# MSO-demo-board.net
KiCad netlist of a schematic drawn in EAGLE
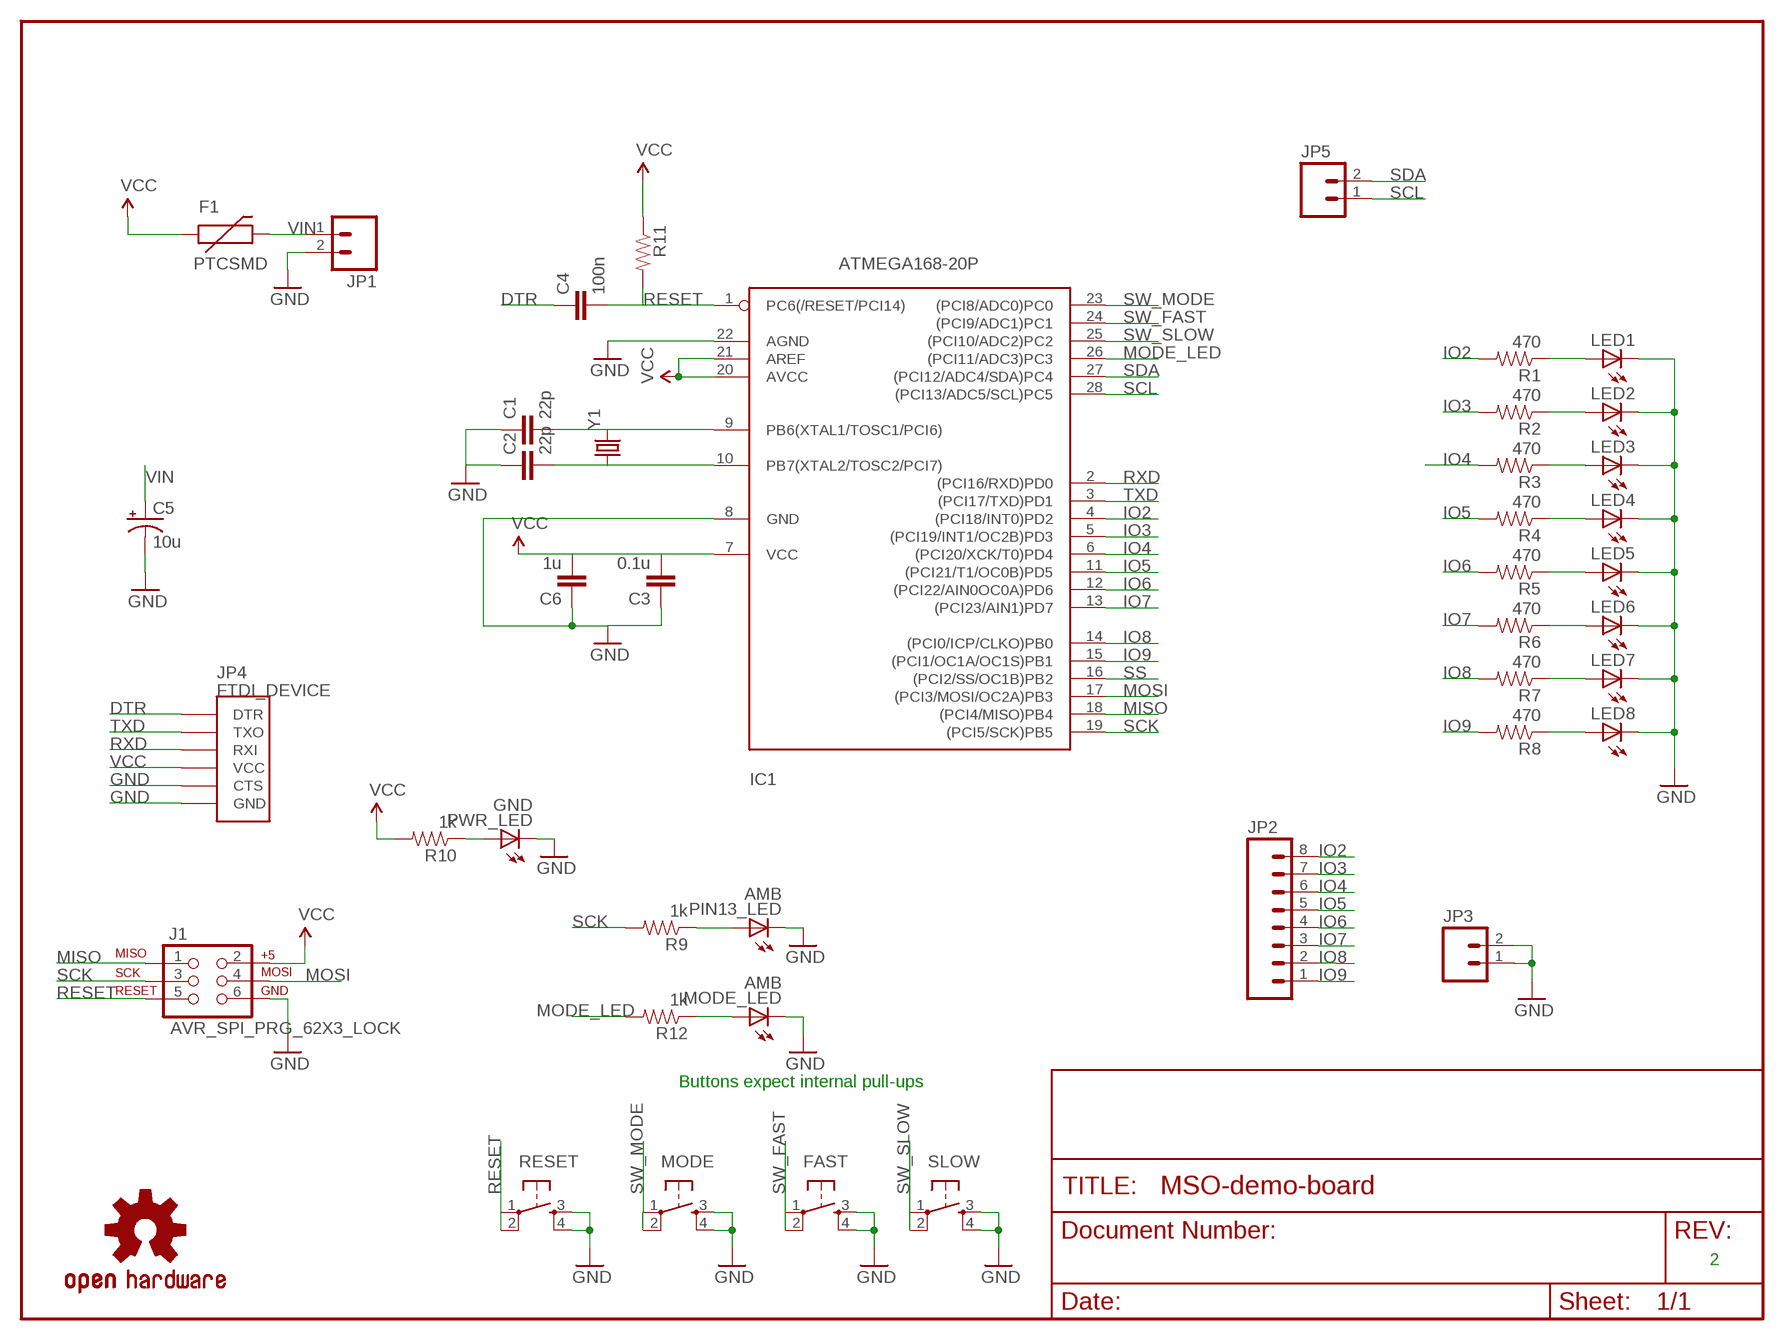
[diagram p0: schematic, sheet 1]

(export (version "E")
  (design (tool "Eeschema 10.0.6"))
  (components
    (comp (ref "C1")
      (value "22p")
      (footprint "eagle-import:1206")
      (libsource (lib "eagle-import") (part "CAP1206"))
    )
    (comp (ref "C2")
      (value "22p")
      (footprint "eagle-import:1206")
      (libsource (lib "eagle-import") (part "CAP1206"))
    )
    (comp (ref "C3")
      (value "0.1u")
      (footprint "eagle-import:1206")
      (libsource (lib "eagle-import") (part "CAP1206"))
    )
    (comp (ref "C4")
      (value "100n")
      (footprint "eagle-import:1206")
      (libsource (lib "eagle-import") (part "CAP1206"))
    )
    (comp (ref "C5")
      (value "10u")
      (footprint "eagle-import:CT7343")
      (libsource (lib "eagle-import") (part "CPOL-USCT7343"))
    )
    (comp (ref "C6")
      (value "1u")
      (footprint "eagle-import:1206")
      (libsource (lib "eagle-import") (part "CAP1206"))
    )
    (comp (ref "F1")
      (value "PTCSMD")
      (footprint "eagle-import:PTC-1206")
      (libsource (lib "eagle-import") (part "PTCSMD"))
    )
    (comp (ref "FAST")
      (value "TAC_SWITCHSMD")
      (footprint "eagle-import:TACTILE_SWITCH_SMD")
      (libsource (lib "eagle-import") (part "TAC_SWITCHSMD"))
    )
    (comp (ref "IC1")
      (value "ATMEGA168-20P")
      (footprint "eagle-import:DIL28-3")
      (libsource (lib "eagle-import") (part "ATMEGA168P-20"))
    )
    (comp (ref "J1")
      (value "AVR_SPI_PRG_62X3_LOCK")
      (footprint "eagle-import:2X3_LOCK")
      (libsource (lib "eagle-import") (part "AVR_SPI_PRG_62X3_LOCK"))
    )
    (comp (ref "JP1")
      (value "M02LOCK")
      (footprint "eagle-import:1X02_LOCK")
      (libsource (lib "eagle-import") (part "M02LOCK"))
    )
    (comp (ref "JP2")
      (value "M08LOCK")
      (footprint "eagle-import:1X08_LOCK")
      (libsource (lib "eagle-import") (part "M08LOCK"))
    )
    (comp (ref "JP3")
      (value "M02LOCK")
      (footprint "eagle-import:1X02_LOCK")
      (libsource (lib "eagle-import") (part "M02LOCK"))
    )
    (comp (ref "JP4")
      (value "FTDI_DEVICE")
      (footprint "eagle-import:FTDI_DEVICE_SIDE")
      (libsource (lib "eagle-import") (part "FTDI_DEVICE"))
    )
    (comp (ref "JP5")
      (value "M02LOCK")
      (footprint "eagle-import:1X02_LOCK")
      (libsource (lib "eagle-import") (part "M02LOCK"))
    )
    (comp (ref "LED1")
      (value "LED1206")
      (footprint "eagle-import:LED-1206")
      (libsource (lib "eagle-import") (part "LED1206"))
    )
    (comp (ref "LED2")
      (value "LED1206")
      (footprint "eagle-import:LED-1206")
      (libsource (lib "eagle-import") (part "LED1206"))
    )
    (comp (ref "LED3")
      (value "LED1206")
      (footprint "eagle-import:LED-1206")
      (libsource (lib "eagle-import") (part "LED1206"))
    )
    (comp (ref "LED4")
      (value "LED1206")
      (footprint "eagle-import:LED-1206")
      (libsource (lib "eagle-import") (part "LED1206"))
    )
    (comp (ref "LED5")
      (value "LED1206")
      (footprint "eagle-import:LED-1206")
      (libsource (lib "eagle-import") (part "LED1206"))
    )
    (comp (ref "LED6")
      (value "LED1206")
      (footprint "eagle-import:LED-1206")
      (libsource (lib "eagle-import") (part "LED1206"))
    )
    (comp (ref "LED7")
      (value "LED1206")
      (footprint "eagle-import:LED-1206")
      (libsource (lib "eagle-import") (part "LED1206"))
    )
    (comp (ref "LED8")
      (value "LED1206")
      (footprint "eagle-import:LED-1206")
      (libsource (lib "eagle-import") (part "LED1206"))
    )
    (comp (ref "MODE")
      (value "TAC_SWITCHSMD")
      (footprint "eagle-import:TACTILE_SWITCH_SMD")
      (libsource (lib "eagle-import") (part "TAC_SWITCHSMD"))
    )
    (comp (ref "MODE_LED")
      (value "AMB")
      (footprint "eagle-import:LED-1206")
      (libsource (lib "eagle-import") (part "LED1206"))
    )
    (comp (ref "PIN13_LED")
      (value "AMB")
      (footprint "eagle-import:LED-1206")
      (libsource (lib "eagle-import") (part "LED1206"))
    )
    (comp (ref "PWR_LED")
      (value "GND")
      (footprint "eagle-import:LED-1206")
      (libsource (lib "eagle-import") (part "LED1206"))
    )
    (comp (ref "R1")
      (value "470")
      (footprint "eagle-import:1206")
      (libsource (lib "eagle-import") (part "RESISTOR1206"))
    )
    (comp (ref "R2")
      (value "470")
      (footprint "eagle-import:1206")
      (libsource (lib "eagle-import") (part "RESISTOR1206"))
    )
    (comp (ref "R3")
      (value "470")
      (footprint "eagle-import:1206")
      (libsource (lib "eagle-import") (part "RESISTOR1206"))
    )
    (comp (ref "R4")
      (value "470")
      (footprint "eagle-import:1206")
      (libsource (lib "eagle-import") (part "RESISTOR1206"))
    )
    (comp (ref "R5")
      (value "470")
      (footprint "eagle-import:1206")
      (libsource (lib "eagle-import") (part "RESISTOR1206"))
    )
    (comp (ref "R6")
      (value "470")
      (footprint "eagle-import:1206")
      (libsource (lib "eagle-import") (part "RESISTOR1206"))
    )
    (comp (ref "R7")
      (value "470")
      (footprint "eagle-import:1206")
      (libsource (lib "eagle-import") (part "RESISTOR1206"))
    )
    (comp (ref "R8")
      (value "470")
      (footprint "eagle-import:1206")
      (libsource (lib "eagle-import") (part "RESISTOR1206"))
    )
    (comp (ref "R9")
      (value "1k")
      (footprint "eagle-import:1206")
      (libsource (lib "eagle-import") (part "RESISTOR1206"))
    )
    (comp (ref "R10")
      (value "1k")
      (footprint "eagle-import:1206")
      (libsource (lib "eagle-import") (part "RESISTOR1206"))
    )
    (comp (ref "R11")
      (value "RESISTOR1206")
      (footprint "eagle-import:1206")
      (libsource (lib "eagle-import") (part "RESISTOR1206"))
    )
    (comp (ref "R12")
      (value "1k")
      (footprint "eagle-import:1206")
      (libsource (lib "eagle-import") (part "RESISTOR1206"))
    )
    (comp (ref "RESET")
      (value "TAC_SWITCHSMD")
      (footprint "eagle-import:TACTILE_SWITCH_SMD")
      (libsource (lib "eagle-import") (part "TAC_SWITCHSMD"))
    )
    (comp (ref "SLOW")
      (value "TAC_SWITCHSMD")
      (footprint "eagle-import:TACTILE_SWITCH_SMD")
      (libsource (lib "eagle-import") (part "TAC_SWITCHSMD"))
    )
    (comp (ref "U$1")
      (value "OSHW-LOGOS")
      (footprint "eagle-import:OSHW-LOGO-S")
      (libsource (lib "eagle-import") (part "OSHW-LOGOS"))
    )
    (comp (ref "Y1")
      (value "CRYSTALHC49UV")
      (footprint "eagle-import:HC49U-V")
      (libsource (lib "eagle-import") (part "CRYSTALHC49UV"))
    )
  )
  (nets
    (net (code "1") (name "/DTR") (class "Default")
      (node (ref "C4") (pin "1") (pinfunction "1_1") (pintype "passive"))
      (node (ref "JP4") (pin "P$1") (pinfunction "DTR_P$1") (pintype "bidirectional"))
    )
    (net (code "2") (name "/IO2") (class "Default")
      (node (ref "IC1") (pin "4") (pinfunction "(PCI18/INT0)PD2_4") (pintype "bidirectional"))
      (node (ref "JP2") (pin "8") (pinfunction "8_8") (pintype "passive"))
      (node (ref "R1") (pin "2") (pinfunction "2_2") (pintype "passive"))
    )
    (net (code "3") (name "/IO3") (class "Default")
      (node (ref "IC1") (pin "5") (pinfunction "(PCI19/INT1/OC2B)PD3_5") (pintype "bidirectional"))
      (node (ref "JP2") (pin "7") (pinfunction "7_7") (pintype "passive"))
      (node (ref "R2") (pin "2") (pinfunction "2_2") (pintype "passive"))
    )
    (net (code "4") (name "/IO4") (class "Default")
      (node (ref "IC1") (pin "6") (pinfunction "(PCI20/XCK/T0)PD4_6") (pintype "bidirectional"))
      (node (ref "JP2") (pin "6") (pinfunction "6_6") (pintype "passive"))
      (node (ref "R3") (pin "2") (pinfunction "2_2") (pintype "passive"))
    )
    (net (code "5") (name "/IO5") (class "Default")
      (node (ref "IC1") (pin "11") (pinfunction "(PCI21/T1/OC0B)PD5_11") (pintype "bidirectional"))
      (node (ref "JP2") (pin "5") (pinfunction "5_5") (pintype "passive"))
      (node (ref "R4") (pin "2") (pinfunction "2_2") (pintype "passive"))
    )
    (net (code "6") (name "/IO6") (class "Default")
      (node (ref "IC1") (pin "12") (pinfunction "(PCI22/AIN0OC0A)PD6_12") (pintype "bidirectional"))
      (node (ref "JP2") (pin "4") (pinfunction "4_4") (pintype "passive"))
      (node (ref "R5") (pin "2") (pinfunction "2_2") (pintype "passive"))
    )
    (net (code "7") (name "/IO7") (class "Default")
      (node (ref "IC1") (pin "13") (pinfunction "(PCI23/AIN1)PD7_13") (pintype "bidirectional"))
      (node (ref "JP2") (pin "3") (pinfunction "3_3") (pintype "passive"))
      (node (ref "R6") (pin "2") (pinfunction "2_2") (pintype "passive"))
    )
    (net (code "8") (name "/IO8") (class "Default")
      (node (ref "IC1") (pin "14") (pinfunction "(PCI0/ICP/CLKO)PB0_14") (pintype "bidirectional"))
      (node (ref "JP2") (pin "2") (pinfunction "2_2") (pintype "passive"))
      (node (ref "R7") (pin "2") (pinfunction "2_2") (pintype "passive"))
    )
    (net (code "9") (name "/IO9") (class "Default")
      (node (ref "IC1") (pin "15") (pinfunction "(PCI1/OC1A/OC1S)PB1_15") (pintype "bidirectional"))
      (node (ref "JP2") (pin "1") (pinfunction "1_1") (pintype "passive"))
      (node (ref "R8") (pin "2") (pinfunction "2_2") (pintype "passive"))
    )
    (net (code "10") (name "/MISO") (class "Default")
      (node (ref "IC1") (pin "18") (pinfunction "(PCI4/MISO)PB4_18") (pintype "bidirectional"))
      (node (ref "J1") (pin "1") (pinfunction "1_1") (pintype "passive"))
    )
    (net (code "11") (name "/MODE_LED") (class "Default")
      (node (ref "IC1") (pin "26") (pinfunction "(PCI11/ADC3)PC3_26") (pintype "bidirectional"))
      (node (ref "R12") (pin "2") (pinfunction "2_2") (pintype "passive"))
    )
    (net (code "12") (name "/MOSI") (class "Default")
      (node (ref "IC1") (pin "17") (pinfunction "(PCI3/MOSI/OC2A)PB3_17") (pintype "bidirectional"))
      (node (ref "J1") (pin "4") (pinfunction "4_4") (pintype "passive"))
    )
    (net (code "13") (name "/RESET") (class "Default")
      (node (ref "C4") (pin "2") (pinfunction "2_2") (pintype "passive"))
      (node (ref "IC1") (pin "1") (pinfunction "PC6(/RESET/PCI14)_1") (pintype "bidirectional"))
      (node (ref "J1") (pin "5") (pinfunction "5_5") (pintype "passive"))
      (node (ref "R11") (pin "2") (pinfunction "2_2") (pintype "passive"))
      (node (ref "RESET") (pin "1") (pinfunction "1_1") (pintype "passive"))
      (node (ref "RESET") (pin "2") (pinfunction "2_2") (pintype "passive"))
    )
    (net (code "14") (name "/RXD") (class "Default")
      (node (ref "IC1") (pin "2") (pinfunction "(PCI16/RXD)PD0_2") (pintype "bidirectional"))
      (node (ref "JP4") (pin "P$3") (pinfunction "RXI_P$3") (pintype "bidirectional"))
    )
    (net (code "15") (name "/SCK") (class "Default")
      (node (ref "IC1") (pin "19") (pinfunction "(PCI5/SCK)PB5_19") (pintype "bidirectional"))
      (node (ref "J1") (pin "3") (pinfunction "3_3") (pintype "passive"))
      (node (ref "R9") (pin "2") (pinfunction "2_2") (pintype "passive"))
    )
    (net (code "16") (name "/SCL") (class "Default")
      (node (ref "IC1") (pin "28") (pinfunction "(PCI13/ADC5/SCL)PC5_28") (pintype "bidirectional"))
      (node (ref "JP5") (pin "1") (pinfunction "1_1") (pintype "passive"))
    )
    (net (code "17") (name "/SDA") (class "Default")
      (node (ref "IC1") (pin "27") (pinfunction "(PCI12/ADC4/SDA)PC4_27") (pintype "bidirectional"))
      (node (ref "JP5") (pin "2") (pinfunction "2_2") (pintype "passive"))
    )
    (net (code "18") (name "/SS") (class "Default")
      (node (ref "IC1") (pin "16") (pinfunction "(PCI2/SS/OC1B)PB2_16") (pintype "bidirectional"))
    )
    (net (code "19") (name "/SW_FAST") (class "Default")
      (node (ref "FAST") (pin "1") (pinfunction "1_1") (pintype "passive"))
      (node (ref "FAST") (pin "2") (pinfunction "2_2") (pintype "passive"))
      (node (ref "IC1") (pin "24") (pinfunction "(PCI9/ADC1)PC1_24") (pintype "bidirectional"))
    )
    (net (code "20") (name "/SW_MODE") (class "Default")
      (node (ref "IC1") (pin "23") (pinfunction "(PCI8/ADC0)PC0_23") (pintype "bidirectional"))
      (node (ref "MODE") (pin "1") (pinfunction "1_1") (pintype "passive"))
      (node (ref "MODE") (pin "2") (pinfunction "2_2") (pintype "passive"))
    )
    (net (code "21") (name "/SW_SLOW") (class "Default")
      (node (ref "IC1") (pin "25") (pinfunction "(PCI10/ADC2)PC2_25") (pintype "bidirectional"))
      (node (ref "SLOW") (pin "1") (pinfunction "1_1") (pintype "passive"))
      (node (ref "SLOW") (pin "2") (pinfunction "2_2") (pintype "passive"))
    )
    (net (code "22") (name "/TXD") (class "Default")
      (node (ref "IC1") (pin "3") (pinfunction "(PCI17/TXD)PD1_3") (pintype "bidirectional"))
      (node (ref "JP4") (pin "P$2") (pinfunction "TXO_P$2") (pintype "bidirectional"))
    )
    (net (code "23") (name "/VIN") (class "Default")
      (node (ref "C5") (pin "+") (pinfunction "+_+") (pintype "passive"))
      (node (ref "F1") (pin "2") (pinfunction "2_2") (pintype "bidirectional"))
      (node (ref "JP1") (pin "1") (pinfunction "1_1") (pintype "passive"))
    )
    (net (code "24") (name "GND") (class "Default")
      (node (ref "C1") (pin "1") (pinfunction "1_1") (pintype "passive"))
      (node (ref "C2") (pin "1") (pinfunction "1_1") (pintype "passive"))
      (node (ref "C3") (pin "1") (pinfunction "1_1") (pintype "passive"))
      (node (ref "C5") (pin "-") (pinfunction "-_-") (pintype "passive"))
      (node (ref "C6") (pin "1") (pinfunction "1_1") (pintype "passive"))
      (node (ref "FAST") (pin "3") (pinfunction "3_3") (pintype "passive"))
      (node (ref "FAST") (pin "4") (pinfunction "4_4") (pintype "passive"))
      (node (ref "IC1") (pin "22") (pinfunction "AGND_22") (pintype "bidirectional"))
      (node (ref "IC1") (pin "8") (pinfunction "GND_8") (pintype "bidirectional"))
      (node (ref "J1") (pin "6") (pinfunction "6_6") (pintype "passive"))
      (node (ref "JP1") (pin "2") (pinfunction "2_2") (pintype "passive"))
      (node (ref "JP3") (pin "1") (pinfunction "1_1") (pintype "passive"))
      (node (ref "JP3") (pin "2") (pinfunction "2_2") (pintype "passive"))
      (node (ref "JP4") (pin "P$5") (pinfunction "CTS_P$5") (pintype "bidirectional"))
      (node (ref "JP4") (pin "P$6") (pinfunction "GND_P$6") (pintype "bidirectional"))
      (node (ref "LED1") (pin "C") (pinfunction "C_C") (pintype "passive"))
      (node (ref "LED2") (pin "C") (pinfunction "C_C") (pintype "passive"))
      (node (ref "LED3") (pin "C") (pinfunction "C_C") (pintype "passive"))
      (node (ref "LED4") (pin "C") (pinfunction "C_C") (pintype "passive"))
      (node (ref "LED5") (pin "C") (pinfunction "C_C") (pintype "passive"))
      (node (ref "LED6") (pin "C") (pinfunction "C_C") (pintype "passive"))
      (node (ref "LED7") (pin "C") (pinfunction "C_C") (pintype "passive"))
      (node (ref "LED8") (pin "C") (pinfunction "C_C") (pintype "passive"))
      (node (ref "MODE") (pin "3") (pinfunction "3_3") (pintype "passive"))
      (node (ref "MODE") (pin "4") (pinfunction "4_4") (pintype "passive"))
      (node (ref "MODE_LED") (pin "C") (pinfunction "C_C") (pintype "passive"))
      (node (ref "PIN13_LED") (pin "C") (pinfunction "C_C") (pintype "passive"))
      (node (ref "PWR_LED") (pin "C") (pinfunction "C_C") (pintype "passive"))
      (node (ref "RESET") (pin "3") (pinfunction "3_3") (pintype "passive"))
      (node (ref "RESET") (pin "4") (pinfunction "4_4") (pintype "passive"))
      (node (ref "SLOW") (pin "3") (pinfunction "3_3") (pintype "passive"))
      (node (ref "SLOW") (pin "4") (pinfunction "4_4") (pintype "passive"))
    )
    (net (code "25") (name "Net-(IC1-PB6(XTAL1{slash}TOSC1{slash}PCI6))") (class "Default")
      (node (ref "C1") (pin "2") (pinfunction "2_2") (pintype "passive"))
      (node (ref "IC1") (pin "9") (pinfunction "PB6(XTAL1/TOSC1/PCI6)_9") (pintype "bidirectional"))
      (node (ref "Y1") (pin "2") (pinfunction "2_2") (pintype "passive"))
    )
    (net (code "26") (name "Net-(IC1-PB7(XTAL2{slash}TOSC2{slash}PCI7))") (class "Default")
      (node (ref "C2") (pin "2") (pinfunction "2_2") (pintype "passive"))
      (node (ref "IC1") (pin "10") (pinfunction "PB7(XTAL2/TOSC2/PCI7)_10") (pintype "bidirectional"))
      (node (ref "Y1") (pin "1") (pinfunction "1_1") (pintype "passive"))
    )
    (net (code "27") (name "Net-(LED1-PadA)") (class "Default")
      (node (ref "LED1") (pin "A") (pinfunction "A_A") (pintype "passive"))
      (node (ref "R1") (pin "1") (pinfunction "1_1") (pintype "passive"))
    )
    (net (code "28") (name "Net-(LED2-PadA)") (class "Default")
      (node (ref "LED2") (pin "A") (pinfunction "A_A") (pintype "passive"))
      (node (ref "R2") (pin "1") (pinfunction "1_1") (pintype "passive"))
    )
    (net (code "29") (name "Net-(LED3-PadA)") (class "Default")
      (node (ref "LED3") (pin "A") (pinfunction "A_A") (pintype "passive"))
      (node (ref "R3") (pin "1") (pinfunction "1_1") (pintype "passive"))
    )
    (net (code "30") (name "Net-(LED4-PadA)") (class "Default")
      (node (ref "LED4") (pin "A") (pinfunction "A_A") (pintype "passive"))
      (node (ref "R4") (pin "1") (pinfunction "1_1") (pintype "passive"))
    )
    (net (code "31") (name "Net-(LED5-PadA)") (class "Default")
      (node (ref "LED5") (pin "A") (pinfunction "A_A") (pintype "passive"))
      (node (ref "R5") (pin "1") (pinfunction "1_1") (pintype "passive"))
    )
    (net (code "32") (name "Net-(LED6-PadA)") (class "Default")
      (node (ref "LED6") (pin "A") (pinfunction "A_A") (pintype "passive"))
      (node (ref "R6") (pin "1") (pinfunction "1_1") (pintype "passive"))
    )
    (net (code "33") (name "Net-(LED7-PadA)") (class "Default")
      (node (ref "LED7") (pin "A") (pinfunction "A_A") (pintype "passive"))
      (node (ref "R7") (pin "1") (pinfunction "1_1") (pintype "passive"))
    )
    (net (code "34") (name "Net-(LED8-PadA)") (class "Default")
      (node (ref "LED8") (pin "A") (pinfunction "A_A") (pintype "passive"))
      (node (ref "R8") (pin "1") (pinfunction "1_1") (pintype "passive"))
    )
    (net (code "35") (name "Net-(MODE_LED-PadA)") (class "Default")
      (node (ref "MODE_LED") (pin "A") (pinfunction "A_A") (pintype "passive"))
      (node (ref "R12") (pin "1") (pinfunction "1_1") (pintype "passive"))
    )
    (net (code "36") (name "Net-(PIN13_LED-PadA)") (class "Default")
      (node (ref "PIN13_LED") (pin "A") (pinfunction "A_A") (pintype "passive"))
      (node (ref "R9") (pin "1") (pinfunction "1_1") (pintype "passive"))
    )
    (net (code "37") (name "Net-(PWR_LED-PadA)") (class "Default")
      (node (ref "PWR_LED") (pin "A") (pinfunction "A_A") (pintype "passive"))
      (node (ref "R10") (pin "1") (pinfunction "1_1") (pintype "passive"))
    )
    (net (code "38") (name "VCC") (class "Default")
      (node (ref "C3") (pin "2") (pinfunction "2_2") (pintype "passive"))
      (node (ref "C6") (pin "2") (pinfunction "2_2") (pintype "passive"))
      (node (ref "F1") (pin "1") (pinfunction "1_1") (pintype "bidirectional"))
      (node (ref "IC1") (pin "20") (pinfunction "AVCC_20") (pintype "bidirectional"))
      (node (ref "IC1") (pin "21") (pinfunction "AREF_21") (pintype "bidirectional"))
      (node (ref "IC1") (pin "7") (pinfunction "VCC_7") (pintype "bidirectional"))
      (node (ref "J1") (pin "2") (pinfunction "2_2") (pintype "passive"))
      (node (ref "JP4") (pin "P$4") (pinfunction "VCC_P$4") (pintype "bidirectional"))
      (node (ref "R10") (pin "2") (pinfunction "2_2") (pintype "passive"))
      (node (ref "R11") (pin "1") (pinfunction "1_1") (pintype "passive"))
    )
  )
)
